# Canal-DDS_V03_R00.net
KiCad netlist of a schematic drawn in Altium Designer
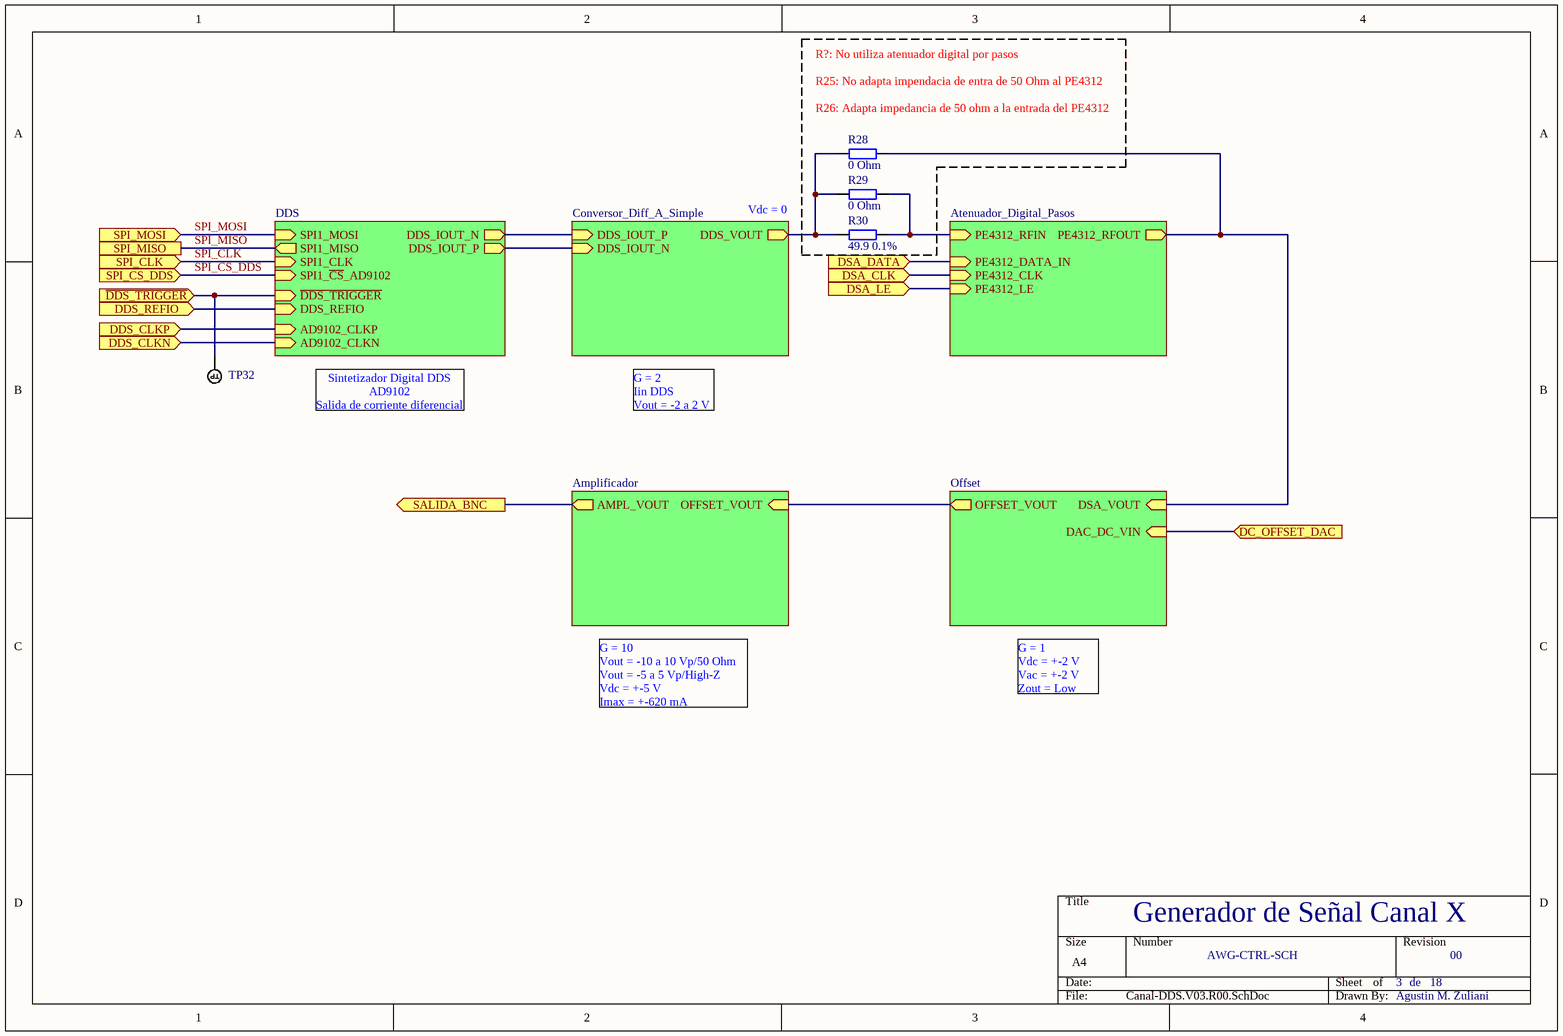
[diagram p0: Canal-DDS.V03.R00.SchDoc]

(export (version "E")
  (design (tool "Eeschema 10.0.6"))
  (components
    (comp (ref "R28")
      (value "0 Ohm")
      (footprint "RES_0805")
      (description "Resistor SMD 0805")
      (libsource (lib "Schematic-Lib-PhilsLab") (part "RES_0805"))
    )
    (comp (ref "R29")
      (value "0 Ohm")
      (footprint "RES_0805")
      (description "Resistor SMD 0805")
      (libsource (lib "Schematic-Lib-PhilsLab") (part "RES_0805"))
    )
    (comp (ref "R30")
      (value "49.9 0.1%")
      (footprint "RES_0805")
      (description "Resistor SMD 0805")
      (libsource (lib "Schematic-Lib-PhilsLab") (part "RES_0805"))
    )
    (comp (ref "TP32")
      (value "TP_NOBOM")
      (footprint "PAD_RND_1MM")
      (description "Test Point Round 1mm (NO BOM)")
      (libsource (lib "Schematic-Lib-PhilsLab") (part "TEST_POINT_RND_1MM"))
    )
  )
  (nets
    (net (code "7") (name "/DDS_TRIGGER") (class "Default")
      (node (ref "TP32") (pin "1") (pinfunction "TP_1") (pintype "passive"))
    )
    (net (code "8") (name "/DDS_VOUT") (class "Default")
      (node (ref "R28") (pin "1") (pinfunction "1_1") (pintype "passive"))
      (node (ref "R29") (pin "1") (pinfunction "1_1") (pintype "passive"))
      (node (ref "R30") (pin "1") (pinfunction "1_1") (pintype "passive"))
    )
    (net (code "13") (name "/PE4312_RFIN") (class "Default")
      (node (ref "R29") (pin "2") (pinfunction "2_2") (pintype "passive"))
      (node (ref "R30") (pin "2") (pinfunction "2_2") (pintype "passive"))
    )
    (net (code "14") (name "/PE4312_RFOUT") (class "Default")
      (node (ref "R28") (pin "2") (pinfunction "2_2") (pintype "passive"))
    )
  )
)
